# SPI_Memory.net
KiCad netlist of a schematic drawn in EAGLE
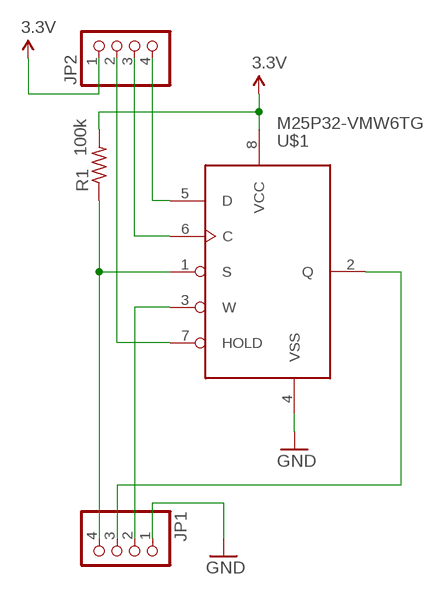
[diagram p0: schematic, sheet 1]

(export (version "E")
  (design (tool "Eeschema 10.0.6"))
  (components
    (comp (ref "JP1")
      (value "PINHD-1X4")
      (footprint "eagle-import:1X04")
      (libsource (lib "eagle-import") (part "PINHD-1X4"))
    )
    (comp (ref "JP2")
      (value "PINHD-1X4")
      (footprint "eagle-import:1X04")
      (libsource (lib "eagle-import") (part "PINHD-1X4"))
    )
    (comp (ref "R1")
      (value "100k")
      (footprint "eagle-import:0603_RESISTOR")
      (libsource (lib "eagle-import") (part "0603_RESISTOR"))
    )
    (comp (ref "U$1")
      (value "M25P32-VMW6TG")
      (footprint "eagle-import:SOIC8_W")
      (libsource (lib "eagle-import") (part "SOIC8-W_MEMORY"))
    )
  )
  (nets
    (net (code "1") (name "3.3V") (class "Default")
      (node (ref "JP2") (pin "1") (pinfunction "1_1") (pintype "passive"))
      (node (ref "R1") (pin "2") (pinfunction "2_2") (pintype "passive"))
      (node (ref "U$1") (pin "8") (pinfunction "VCC_8") (pintype "power_in"))
    )
    (net (code "2") (name "GND") (class "Default")
      (node (ref "JP1") (pin "1") (pinfunction "1_1") (pintype "passive"))
      (node (ref "U$1") (pin "4") (pinfunction "VSS_4") (pintype "power_in"))
    )
    (net (code "3") (name "Net-(U$1-C)") (class "Default")
      (node (ref "JP2") (pin "3") (pinfunction "3_3") (pintype "passive"))
      (node (ref "U$1") (pin "6") (pinfunction "C_6") (pintype "input"))
    )
    (net (code "4") (name "Net-(U$1-D)") (class "Default")
      (node (ref "JP2") (pin "4") (pinfunction "4_4") (pintype "passive"))
      (node (ref "U$1") (pin "5") (pinfunction "D_5") (pintype "input"))
    )
    (net (code "5") (name "Net-(U$1-HOLD)") (class "Default")
      (node (ref "JP2") (pin "2") (pinfunction "2_2") (pintype "passive"))
      (node (ref "U$1") (pin "7") (pinfunction "HOLD_7") (pintype "input"))
    )
    (net (code "6") (name "Net-(U$1-Q)") (class "Default")
      (node (ref "JP1") (pin "3") (pinfunction "3_3") (pintype "passive"))
      (node (ref "U$1") (pin "2") (pinfunction "Q_2") (pintype "output"))
    )
    (net (code "7") (name "Net-(U$1-S)") (class "Default")
      (node (ref "JP1") (pin "4") (pinfunction "4_4") (pintype "passive"))
      (node (ref "R1") (pin "1") (pinfunction "1_1") (pintype "passive"))
      (node (ref "U$1") (pin "1") (pinfunction "S_1") (pintype "input"))
    )
    (net (code "8") (name "Net-(U$1-W)") (class "Default")
      (node (ref "JP1") (pin "2") (pinfunction "2_2") (pintype "passive"))
      (node (ref "U$1") (pin "3") (pinfunction "W_3") (pintype "input"))
    )
  )
)
